# Wilssen_core_v0_202a.net
KiCad netlist of a schematic drawn in EAGLE
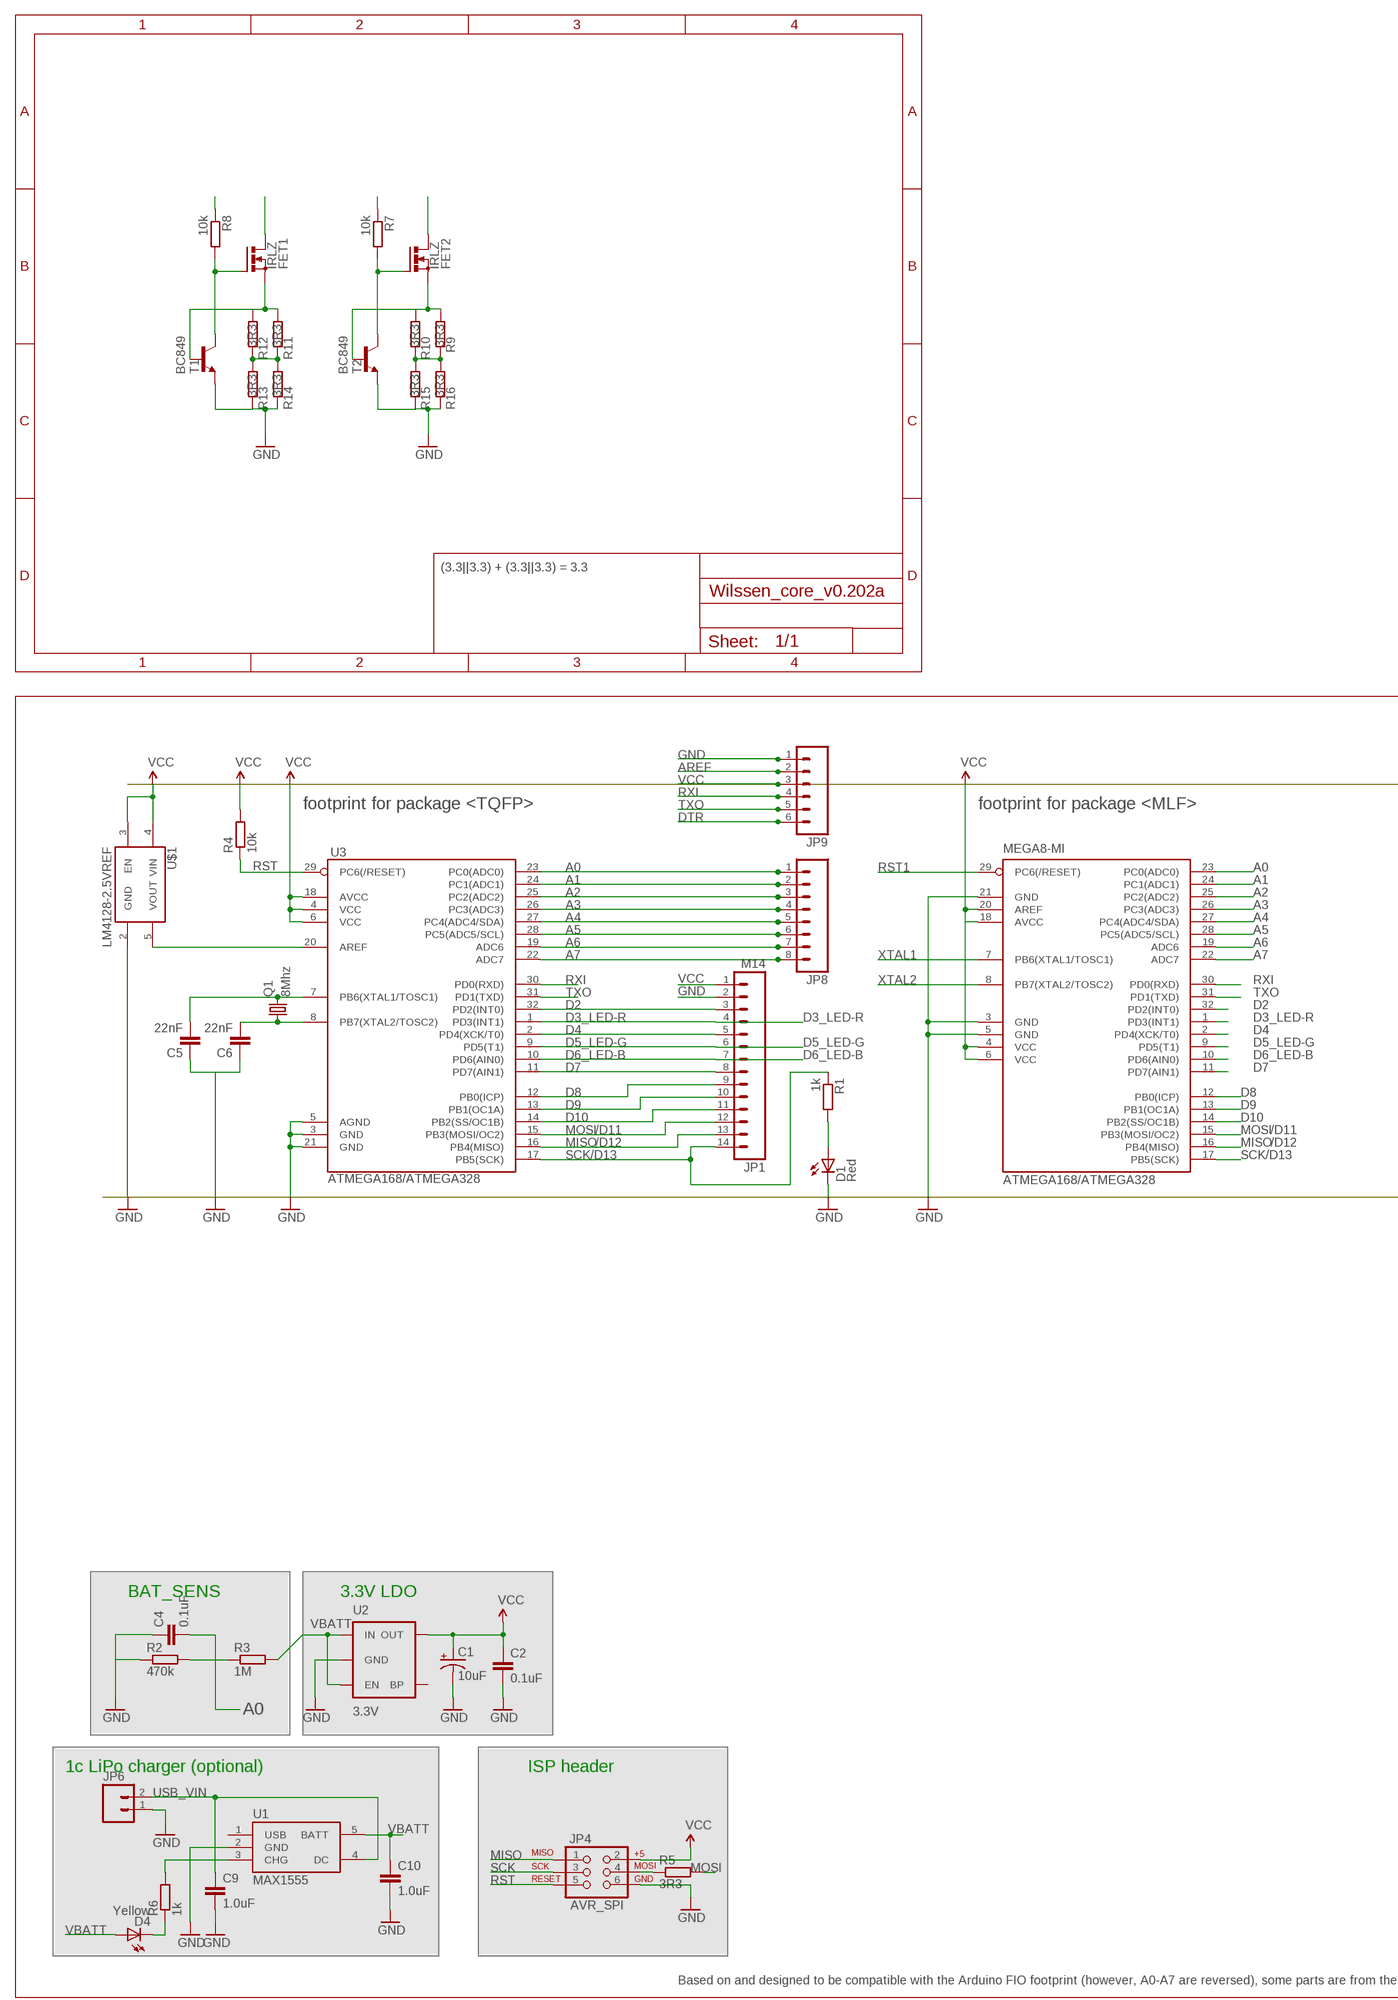
[diagram p0: schematic, sheet 1, part 1 of 2]
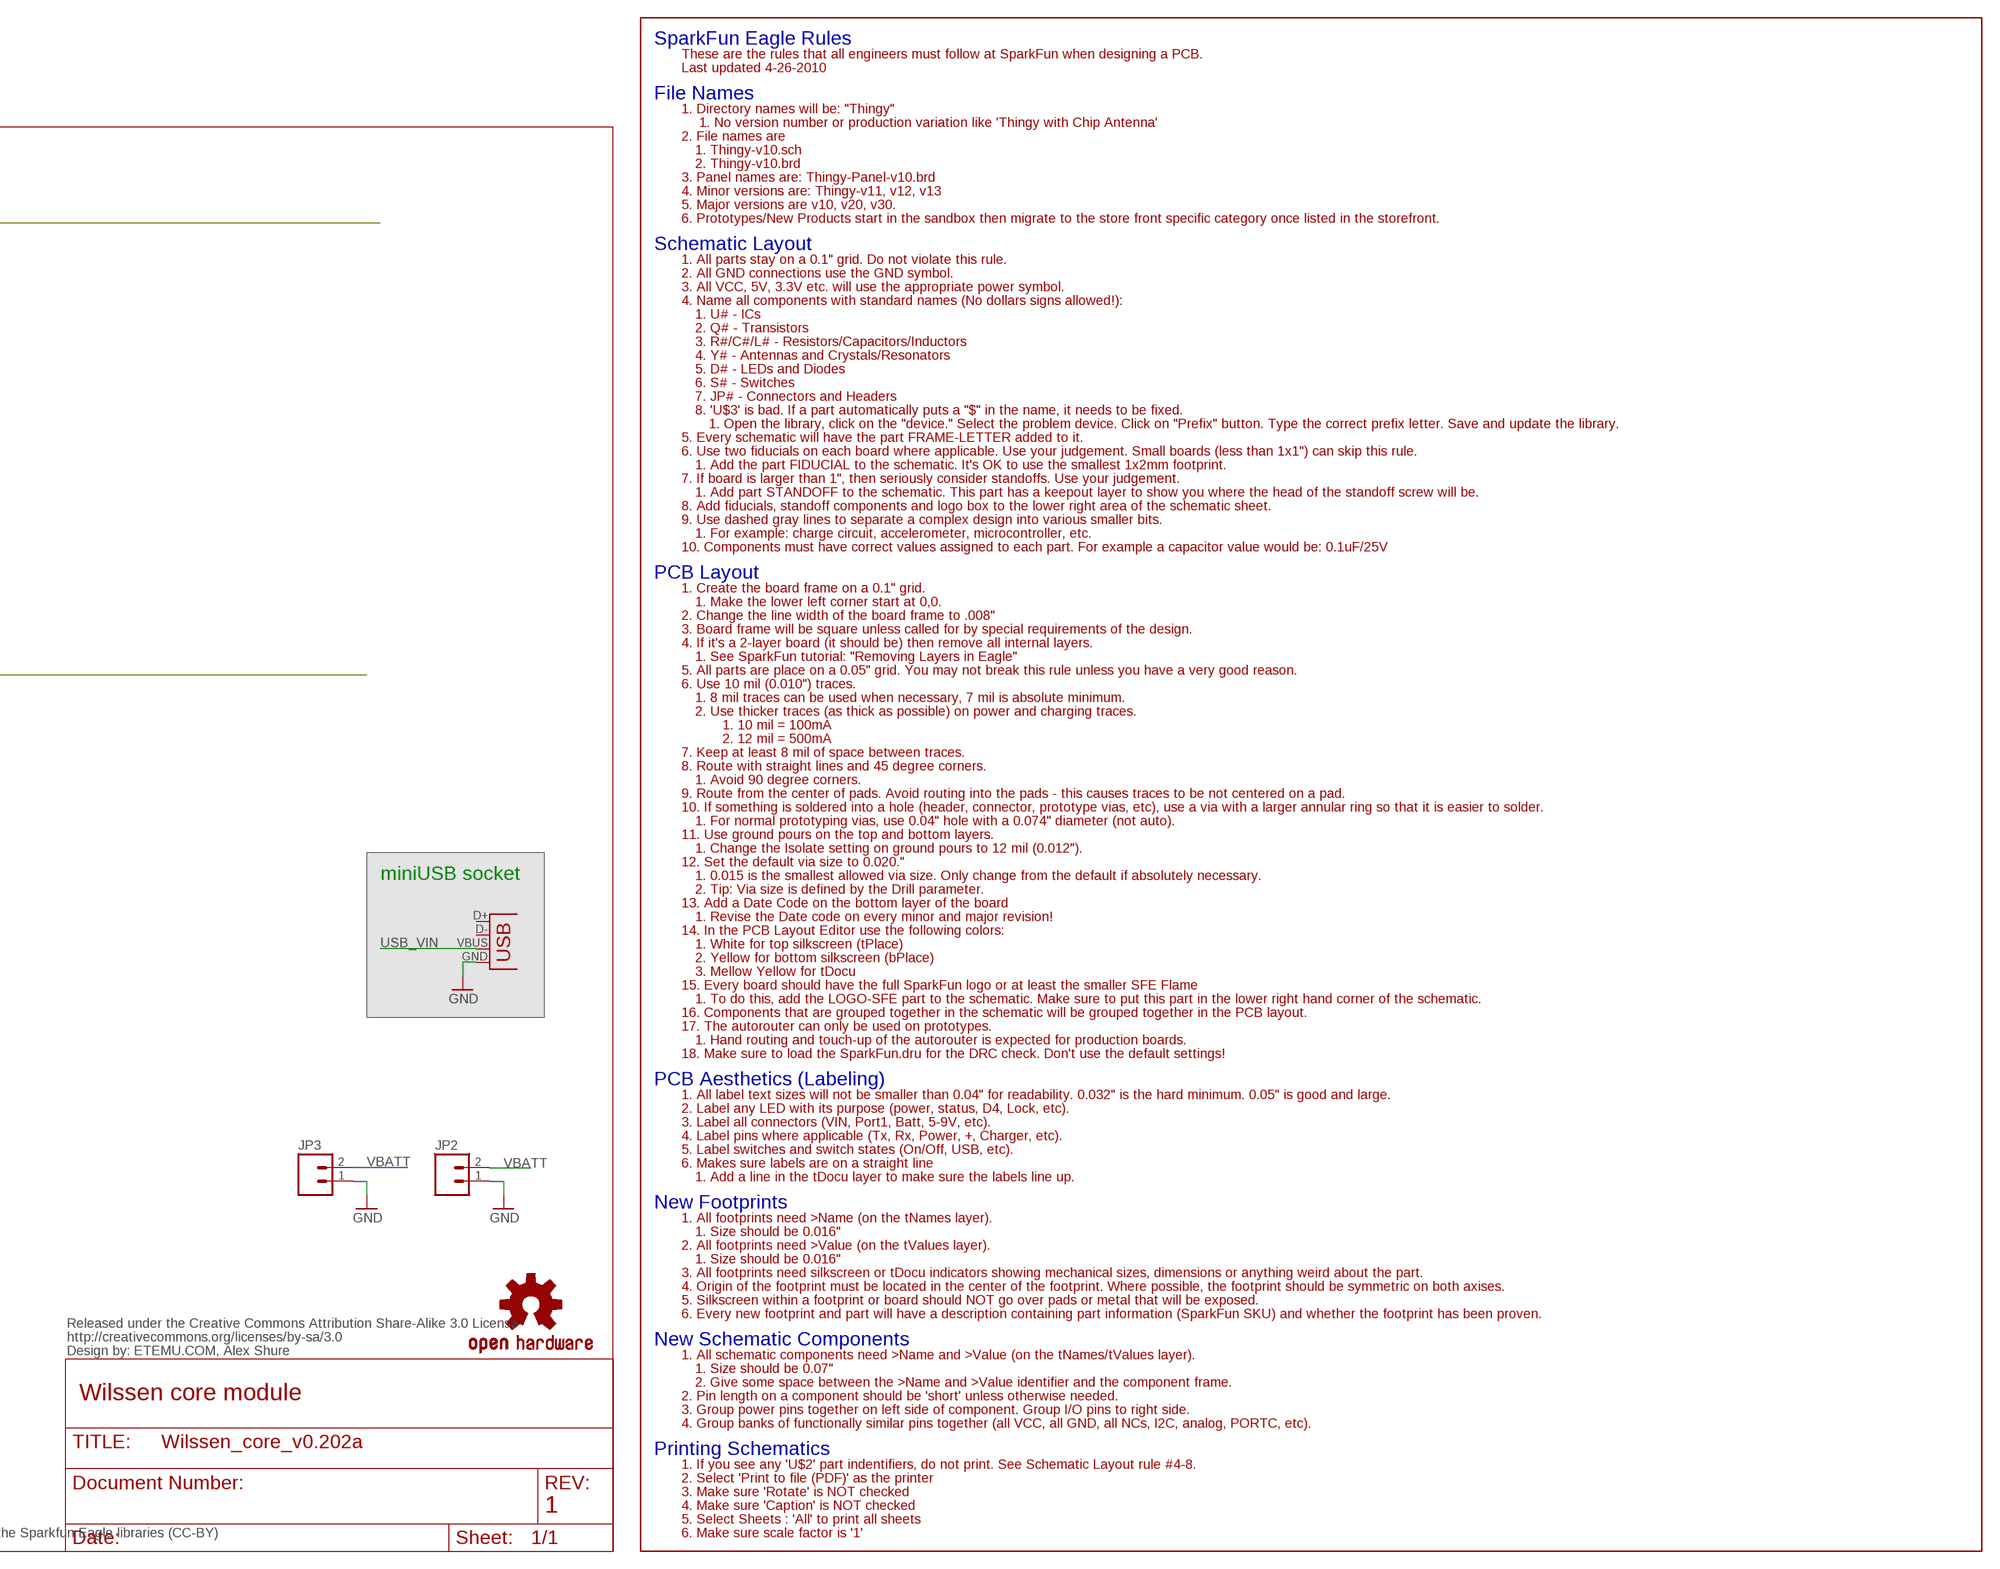
[diagram p1: schematic, sheet 1, part 2 of 2]

(export (version "E")
  (design (tool "Eeschema 10.0.6"))
  (components
    (comp (ref "ATMEGA168/ATMEGA328")
      (value "MEGA8-MI")
      (footprint "eagle-import:MLF32")
      (fields (field (name "MPN") "ATMEGA88PA-MU"))
      (libsource (lib "eagle-import") (part "MEGA8-MI"))
    )
    (comp (ref "C1")
      (value "10uF")
      (footprint "eagle-import:EIA3216")
      (libsource (lib "eagle-import") (part "CAP_POL1206"))
    )
    (comp (ref "C2")
      (value "0.1uF")
      (footprint "eagle-import:0805")
      (libsource (lib "eagle-import") (part "CAP0805"))
    )
    (comp (ref "C4")
      (value "0.1uF")
      (footprint "eagle-import:0805")
      (libsource (lib "eagle-import") (part "CAP0805"))
    )
    (comp (ref "C5")
      (value "22nF")
      (footprint "eagle-import:0805")
      (libsource (lib "eagle-import") (part "CAP0805"))
    )
    (comp (ref "C6")
      (value "22nF")
      (footprint "eagle-import:0805")
      (libsource (lib "eagle-import") (part "CAP0805"))
    )
    (comp (ref "C9")
      (value "1.0uF")
      (footprint "eagle-import:0805")
      (libsource (lib "eagle-import") (part "CAP0805"))
    )
    (comp (ref "C10")
      (value "1.0uF")
      (footprint "eagle-import:0805")
      (libsource (lib "eagle-import") (part "CAP0805"))
    )
    (comp (ref "CC_TEXT1")
      (value "CREATIVE_COMMONS")
      (footprint "eagle-import:CREATIVE_COMMONS")
      (libsource (lib "eagle-import") (part "CREATIVE_COMMONS"))
    )
    (comp (ref "D1")
      (value "Red")
      (footprint "eagle-import:LED-0603")
      (libsource (lib "eagle-import") (part "LED0603"))
    )
    (comp (ref "D4")
      (value "Yellow")
      (footprint "eagle-import:LED-0603")
      (libsource (lib "eagle-import") (part "LED0603"))
    )
    (comp (ref "FET1")
      (value "IRLZ")
      (footprint "eagle-import:TO220BV")
      (libsource (lib "eagle-import") (part "PMOSFET_NTO220BV"))
    )
    (comp (ref "FET2")
      (value "IRLZ")
      (footprint "eagle-import:TO220BV")
      (libsource (lib "eagle-import") (part "PMOSFET_NTO220BV"))
    )
    (comp (ref "JP1")
      (value "M14")
      (footprint "eagle-import:1X14")
      (libsource (lib "eagle-import") (part "M14"))
    )
    (comp (ref "JP2")
      (value "M02PTH")
      (footprint "eagle-import:1X02")
      (libsource (lib "eagle-import") (part "M02PTH"))
    )
    (comp (ref "JP3")
      (value "M02-JST-2MM-SMT")
      (footprint "eagle-import:S2B-PH")
      (libsource (lib "eagle-import") (part "M02-JST-2MM-SMT"))
    )
    (comp (ref "JP4")
      (value "AVR_SPI")
      (footprint "eagle-import:2X3")
      (libsource (lib "eagle-import") (part "AVR_SPI_PRG_6PTH"))
    )
    (comp (ref "JP6")
      (value "M02PTH")
      (footprint "eagle-import:1X02")
      (libsource (lib "eagle-import") (part "M02PTH"))
    )
    (comp (ref "JP8")
      (value "M081X08")
      (footprint "eagle-import:1X08")
      (libsource (lib "eagle-import") (part "M081X08"))
    )
    (comp (ref "JP9")
      (value "M06SIP")
      (footprint "eagle-import:1X06")
      (libsource (lib "eagle-import") (part "M06SIP"))
    )
    (comp (ref "LOGO1")
      (value "OSHW-LOGOS")
      (footprint "eagle-import:OSHW-LOGO-S")
      (libsource (lib "eagle-import") (part "OSHW-LOGOS"))
    )
    (comp (ref "Q1")
      (value "8Mhz")
      (footprint "eagle-import:SM49")
      (libsource (lib "eagle-import") (part "CRYSTALSM49"))
    )
    (comp (ref "R1")
      (value "1k")
      (footprint "eagle-import:R0805")
      (libsource (lib "eagle-import") (part "R-EU_R0805"))
    )
    (comp (ref "R2")
      (value "470k")
      (footprint "eagle-import:R0805")
      (libsource (lib "eagle-import") (part "R-EU_R0805"))
    )
    (comp (ref "R3")
      (value "1M")
      (footprint "eagle-import:R0805")
      (libsource (lib "eagle-import") (part "R-EU_R0805"))
    )
    (comp (ref "R4")
      (value "10k")
      (footprint "eagle-import:R0805")
      (libsource (lib "eagle-import") (part "R-EU_R0805"))
    )
    (comp (ref "R5")
      (value "3R3")
      (footprint "eagle-import:R1206")
      (libsource (lib "eagle-import") (part "R-EU_R1206"))
    )
    (comp (ref "R6")
      (value "1k")
      (footprint "eagle-import:R0805")
      (libsource (lib "eagle-import") (part "R-EU_R0805"))
    )
    (comp (ref "R7")
      (value "10k")
      (footprint "eagle-import:R0805")
      (libsource (lib "eagle-import") (part "resistor_R-EU_R0805"))
    )
    (comp (ref "R8")
      (value "10k")
      (footprint "eagle-import:R0805")
      (libsource (lib "eagle-import") (part "resistor_R-EU_R0805"))
    )
    (comp (ref "R9")
      (value "3R3")
      (footprint "eagle-import:R1206")
      (libsource (lib "eagle-import") (part "resistor_R-EU_R1206"))
    )
    (comp (ref "R10")
      (value "3R3")
      (footprint "eagle-import:R1206")
      (libsource (lib "eagle-import") (part "resistor_R-EU_R1206"))
    )
    (comp (ref "R11")
      (value "3R3")
      (footprint "eagle-import:R1206")
      (libsource (lib "eagle-import") (part "resistor_R-EU_R1206"))
    )
    (comp (ref "R12")
      (value "3R3")
      (footprint "eagle-import:R1206")
      (libsource (lib "eagle-import") (part "resistor_R-EU_R1206"))
    )
    (comp (ref "R13")
      (value "3R3")
      (footprint "eagle-import:R1206")
      (libsource (lib "eagle-import") (part "resistor_R-EU_R1206"))
    )
    (comp (ref "R14")
      (value "3R3")
      (footprint "eagle-import:R1206")
      (libsource (lib "eagle-import") (part "resistor_R-EU_R1206"))
    )
    (comp (ref "R15")
      (value "3R3")
      (footprint "eagle-import:R1206")
      (libsource (lib "eagle-import") (part "resistor_R-EU_R1206"))
    )
    (comp (ref "R16")
      (value "3R3")
      (footprint "eagle-import:R1206")
      (libsource (lib "eagle-import") (part "resistor_R-EU_R1206"))
    )
    (comp (ref "T1")
      (value "BC849")
      (footprint "eagle-import:SOT23")
      (libsource (lib "eagle-import") (part "BC849"))
    )
    (comp (ref "T2")
      (value "BC849")
      (footprint "eagle-import:SOT23")
      (libsource (lib "eagle-import") (part "BC849"))
    )
    (comp (ref "U$1")
      (value "LM4128-2.5VREF")
      (footprint "eagle-import:SOT23-5")
      (libsource (lib "eagle-import") (part "LM4128-2.5VREF"))
    )
    (comp (ref "U1")
      (value "MAX1555")
      (footprint "eagle-import:SOT23-5")
      (libsource (lib "eagle-import") (part "MAX1555"))
    )
    (comp (ref "U2")
      (value "3.3V")
      (footprint "eagle-import:SOT23-5")
      (libsource (lib "eagle-import") (part "V_REG_LDOSMD"))
    )
    (comp (ref "U3")
      (value "ATMEGA168/ATMEGA328")
      (footprint "eagle-import:TQFP32-08")
      (libsource (lib "eagle-import") (part "ATMEGA168"))
    )
    (comp (ref "X1")
      (value "USBSMD")
      (footprint "eagle-import:USB-MINIB")
      (libsource (lib "eagle-import") (part "USBSMD"))
    )
  )
  (nets
    (net (code "1") (name "/A0") (class "Default")
      (node (ref "ATMEGA168/ATMEGA328") (pin "23") (pinfunction "PC0(ADC0)_23") (pintype "bidirectional"))
      (node (ref "C4") (pin "2") (pinfunction "2_2") (pintype "passive"))
      (node (ref "JP8") (pin "1") (pinfunction "1_1") (pintype "passive"))
      (node (ref "R2") (pin "2") (pinfunction "2_2") (pintype "passive"))
      (node (ref "R3") (pin "1") (pinfunction "1_1") (pintype "passive"))
      (node (ref "U3") (pin "23") (pinfunction "PC0(ADC0)_23") (pintype "bidirectional"))
    )
    (net (code "2") (name "/A1") (class "Default")
      (node (ref "ATMEGA168/ATMEGA328") (pin "24") (pinfunction "PC1(ADC1)_24") (pintype "bidirectional"))
      (node (ref "JP8") (pin "2") (pinfunction "2_2") (pintype "passive"))
      (node (ref "U3") (pin "24") (pinfunction "PC1(ADC1)_24") (pintype "bidirectional"))
    )
    (net (code "3") (name "/A2") (class "Default")
      (node (ref "ATMEGA168/ATMEGA328") (pin "25") (pinfunction "PC2(ADC2)_25") (pintype "bidirectional"))
      (node (ref "JP8") (pin "3") (pinfunction "3_3") (pintype "passive"))
      (node (ref "U3") (pin "25") (pinfunction "PC2(ADC2)_25") (pintype "bidirectional"))
    )
    (net (code "4") (name "/A3") (class "Default")
      (node (ref "ATMEGA168/ATMEGA328") (pin "26") (pinfunction "PC3(ADC3)_26") (pintype "bidirectional"))
      (node (ref "JP8") (pin "4") (pinfunction "4_4") (pintype "passive"))
      (node (ref "U3") (pin "26") (pinfunction "PC3(ADC3)_26") (pintype "bidirectional"))
    )
    (net (code "5") (name "/A4") (class "Default")
      (node (ref "ATMEGA168/ATMEGA328") (pin "27") (pinfunction "PC4(ADC4/SDA)_27") (pintype "bidirectional"))
      (node (ref "JP8") (pin "5") (pinfunction "5_5") (pintype "passive"))
      (node (ref "U3") (pin "27") (pinfunction "PC4(ADC4/SDA)_27") (pintype "bidirectional"))
    )
    (net (code "6") (name "/A5") (class "Default")
      (node (ref "ATMEGA168/ATMEGA328") (pin "28") (pinfunction "PC5(ADC5/SCL)_28") (pintype "bidirectional"))
      (node (ref "JP8") (pin "6") (pinfunction "6_6") (pintype "passive"))
      (node (ref "U3") (pin "28") (pinfunction "PC5(ADC5/SCL)_28") (pintype "bidirectional"))
    )
    (net (code "7") (name "/A6") (class "Default")
      (node (ref "ATMEGA168/ATMEGA328") (pin "19") (pinfunction "ADC6_19") (pintype "bidirectional"))
      (node (ref "JP8") (pin "7") (pinfunction "7_7") (pintype "passive"))
      (node (ref "U3") (pin "19") (pinfunction "ADC6_19") (pintype "bidirectional"))
    )
    (net (code "8") (name "/A7") (class "Default")
      (node (ref "ATMEGA168/ATMEGA328") (pin "22") (pinfunction "ADC7_22") (pintype "bidirectional"))
      (node (ref "JP8") (pin "8") (pinfunction "8_8") (pintype "passive"))
      (node (ref "U3") (pin "22") (pinfunction "ADC7_22") (pintype "bidirectional"))
    )
    (net (code "9") (name "/AREF") (class "Default")
      (node (ref "JP9") (pin "2") (pinfunction "2_2") (pintype "passive"))
    )
    (net (code "10") (name "/D2") (class "Default")
      (node (ref "ATMEGA168/ATMEGA328") (pin "32") (pinfunction "PD2(INT0)_32") (pintype "bidirectional"))
      (node (ref "JP1") (pin "3") (pinfunction "3_3") (pintype "passive"))
      (node (ref "U3") (pin "32") (pinfunction "PD2(INT0)_32") (pintype "bidirectional"))
    )
    (net (code "11") (name "/D3_LED-R") (class "Default")
      (node (ref "ATMEGA168/ATMEGA328") (pin "1") (pinfunction "PD3(INT1)_1") (pintype "bidirectional"))
      (node (ref "JP1") (pin "4") (pinfunction "4_4") (pintype "passive"))
      (node (ref "R8") (pin "1") (pinfunction "1_1") (pintype "passive"))
      (node (ref "U3") (pin "1") (pinfunction "PD3(INT1)_1") (pintype "bidirectional"))
    )
    (net (code "12") (name "/D4") (class "Default")
      (node (ref "ATMEGA168/ATMEGA328") (pin "2") (pinfunction "PD4(XCK/T0)_2") (pintype "bidirectional"))
      (node (ref "JP1") (pin "5") (pinfunction "5_5") (pintype "passive"))
      (node (ref "U3") (pin "2") (pinfunction "PD4(XCK/T0)_2") (pintype "bidirectional"))
    )
    (net (code "13") (name "/D5_LED-G") (class "Default")
      (node (ref "ATMEGA168/ATMEGA328") (pin "9") (pinfunction "PD5(T1)_9") (pintype "bidirectional"))
      (node (ref "JP1") (pin "6") (pinfunction "6_6") (pintype "passive"))
      (node (ref "R7") (pin "1") (pinfunction "1_1") (pintype "passive"))
      (node (ref "U3") (pin "9") (pinfunction "PD5(T1)_9") (pintype "bidirectional"))
    )
    (net (code "14") (name "/D6_LED-B") (class "Default")
      (node (ref "ATMEGA168/ATMEGA328") (pin "10") (pinfunction "PD6(AIN0)_10") (pintype "bidirectional"))
      (node (ref "JP1") (pin "7") (pinfunction "7_7") (pintype "passive"))
      (node (ref "U3") (pin "10") (pinfunction "PD6(AIN0)_10") (pintype "bidirectional"))
    )
    (net (code "15") (name "/D7") (class "Default")
      (node (ref "ATMEGA168/ATMEGA328") (pin "11") (pinfunction "PD7(AIN1)_11") (pintype "bidirectional"))
      (node (ref "JP1") (pin "8") (pinfunction "8_8") (pintype "passive"))
      (node (ref "U3") (pin "11") (pinfunction "PD7(AIN1)_11") (pintype "bidirectional"))
    )
    (net (code "16") (name "/D8") (class "Default")
      (node (ref "ATMEGA168/ATMEGA328") (pin "12") (pinfunction "PB0(ICP)_12") (pintype "bidirectional"))
      (node (ref "JP1") (pin "9") (pinfunction "9_9") (pintype "passive"))
      (node (ref "U3") (pin "12") (pinfunction "PB0(ICP)_12") (pintype "bidirectional"))
    )
    (net (code "17") (name "/D9") (class "Default")
      (node (ref "ATMEGA168/ATMEGA328") (pin "13") (pinfunction "PB1(OC1A)_13") (pintype "bidirectional"))
      (node (ref "JP1") (pin "10") (pinfunction "10_10") (pintype "passive"))
      (node (ref "U3") (pin "13") (pinfunction "PB1(OC1A)_13") (pintype "bidirectional"))
    )
    (net (code "18") (name "/D10") (class "Default")
      (node (ref "ATMEGA168/ATMEGA328") (pin "14") (pinfunction "PB2(SS/OC1B)_14") (pintype "bidirectional"))
      (node (ref "JP1") (pin "11") (pinfunction "11_11") (pintype "passive"))
      (node (ref "U3") (pin "14") (pinfunction "PB2(SS/OC1B)_14") (pintype "bidirectional"))
    )
    (net (code "19") (name "/DTR") (class "Default")
      (node (ref "JP9") (pin "6") (pinfunction "6_6") (pintype "passive"))
    )
    (net (code "20") (name "/MISO") (class "Default")
      (node (ref "ATMEGA168/ATMEGA328") (pin "16") (pinfunction "PB4(MISO)_16") (pintype "bidirectional"))
      (node (ref "JP1") (pin "13") (pinfunction "13_13") (pintype "passive"))
      (node (ref "JP4") (pin "1") (pinfunction "1_1") (pintype "passive"))
      (node (ref "U3") (pin "16") (pinfunction "PB4(MISO)_16") (pintype "bidirectional"))
    )
    (net (code "21") (name "/MOSI") (class "Default")
      (node (ref "ATMEGA168/ATMEGA328") (pin "15") (pinfunction "PB3(MOSI/OC2)_15") (pintype "bidirectional"))
      (node (ref "JP1") (pin "12") (pinfunction "12_12") (pintype "passive"))
      (node (ref "R5") (pin "2") (pinfunction "2_2") (pintype "passive"))
      (node (ref "U3") (pin "15") (pinfunction "PB3(MOSI/OC2)_15") (pintype "bidirectional"))
    )
    (net (code "22") (name "/RST") (class "Default")
      (node (ref "JP4") (pin "5") (pinfunction "5_5") (pintype "passive"))
      (node (ref "R4") (pin "1") (pinfunction "1_1") (pintype "passive"))
      (node (ref "U3") (pin "29") (pinfunction "PC6(/RESET)_29") (pintype "bidirectional"))
    )
    (net (code "23") (name "/RST1") (class "Default")
      (node (ref "ATMEGA168/ATMEGA328") (pin "29") (pinfunction "PC6(/RESET)_29") (pintype "bidirectional"))
    )
    (net (code "24") (name "/RXI") (class "Default")
      (node (ref "ATMEGA168/ATMEGA328") (pin "30") (pinfunction "PD0(RXD)_30") (pintype "bidirectional"))
      (node (ref "JP9") (pin "4") (pinfunction "4_4") (pintype "passive"))
      (node (ref "U3") (pin "30") (pinfunction "PD0(RXD)_30") (pintype "bidirectional"))
    )
    (net (code "25") (name "/SCK") (class "Default")
      (node (ref "ATMEGA168/ATMEGA328") (pin "17") (pinfunction "PB5(SCK)_17") (pintype "bidirectional"))
      (node (ref "JP1") (pin "14") (pinfunction "14_14") (pintype "passive"))
      (node (ref "JP4") (pin "3") (pinfunction "3_3") (pintype "passive"))
      (node (ref "R1") (pin "1") (pinfunction "1_1") (pintype "passive"))
      (node (ref "U3") (pin "17") (pinfunction "PB5(SCK)_17") (pintype "bidirectional"))
    )
    (net (code "26") (name "/TXO") (class "Default")
      (node (ref "ATMEGA168/ATMEGA328") (pin "31") (pinfunction "PD1(TXD)_31") (pintype "bidirectional"))
      (node (ref "JP9") (pin "5") (pinfunction "5_5") (pintype "passive"))
      (node (ref "U3") (pin "31") (pinfunction "PD1(TXD)_31") (pintype "bidirectional"))
    )
    (net (code "27") (name "/USB_VIN") (class "Default")
      (node (ref "C9") (pin "1") (pinfunction "1_1") (pintype "passive"))
      (node (ref "JP6") (pin "2") (pinfunction "2_2") (pintype "passive"))
      (node (ref "U1") (pin "4") (pinfunction "DC_4") (pintype "bidirectional"))
      (node (ref "X1") (pin "VBUS") (pinfunction "VBUS_VBUS") (pintype "bidirectional"))
    )
    (net (code "28") (name "/VBATT") (class "Default")
      (node (ref "C10") (pin "1") (pinfunction "1_1") (pintype "passive"))
      (node (ref "D4") (pin "A") (pinfunction "A_A") (pintype "passive"))
      (node (ref "JP2") (pin "2") (pinfunction "2_2") (pintype "passive"))
      (node (ref "JP3") (pin "2") (pinfunction "2_2") (pintype "passive"))
      (node (ref "R3") (pin "2") (pinfunction "2_2") (pintype "passive"))
      (node (ref "U1") (pin "5") (pinfunction "BATT_5") (pintype "bidirectional"))
      (node (ref "U2") (pin "1") (pinfunction "IN_1") (pintype "input"))
      (node (ref "U2") (pin "3") (pinfunction "EN_3") (pintype "input"))
    )
    (net (code "29") (name "/XTAL1") (class "Default")
      (node (ref "ATMEGA168/ATMEGA328") (pin "7") (pinfunction "PB6(XTAL1/TOSC1)_7") (pintype "bidirectional"))
      (node (ref "C5") (pin "2") (pinfunction "2_2") (pintype "passive"))
      (node (ref "Q1") (pin "2") (pinfunction "2_2") (pintype "passive"))
      (node (ref "U3") (pin "7") (pinfunction "PB6(XTAL1/TOSC1)_7") (pintype "bidirectional"))
    )
    (net (code "30") (name "/XTAL2") (class "Default")
      (node (ref "ATMEGA168/ATMEGA328") (pin "8") (pinfunction "PB7(XTAL2/TOSC2)_8") (pintype "bidirectional"))
      (node (ref "C6") (pin "2") (pinfunction "2_2") (pintype "passive"))
      (node (ref "Q1") (pin "1") (pinfunction "1_1") (pintype "passive"))
      (node (ref "U3") (pin "8") (pinfunction "PB7(XTAL2/TOSC2)_8") (pintype "bidirectional"))
    )
    (net (code "31") (name "GND") (class "Default")
      (node (ref "ATMEGA168/ATMEGA328") (pin "21") (pinfunction "GND_21") (pintype "power_in"))
      (node (ref "ATMEGA168/ATMEGA328") (pin "3") (pinfunction "GND_3") (pintype "power_in"))
      (node (ref "ATMEGA168/ATMEGA328") (pin "5") (pinfunction "GND_5") (pintype "power_in"))
      (node (ref "C1") (pin "C") (pinfunction "-_C") (pintype "passive"))
      (node (ref "C10") (pin "2") (pinfunction "2_2") (pintype "passive"))
      (node (ref "C2") (pin "2") (pinfunction "2_2") (pintype "passive"))
      (node (ref "C4") (pin "1") (pinfunction "1_1") (pintype "passive"))
      (node (ref "C5") (pin "1") (pinfunction "1_1") (pintype "passive"))
      (node (ref "C6") (pin "1") (pinfunction "1_1") (pintype "passive"))
      (node (ref "C9") (pin "2") (pinfunction "2_2") (pintype "passive"))
      (node (ref "D1") (pin "C") (pinfunction "C_C") (pintype "passive"))
      (node (ref "JP1") (pin "2") (pinfunction "2_2") (pintype "passive"))
      (node (ref "JP2") (pin "1") (pinfunction "1_1") (pintype "passive"))
      (node (ref "JP3") (pin "1") (pinfunction "1_1") (pintype "passive"))
      (node (ref "JP4") (pin "6") (pinfunction "6_6") (pintype "passive"))
      (node (ref "JP6") (pin "1") (pinfunction "1_1") (pintype "passive"))
      (node (ref "JP9") (pin "1") (pinfunction "1_1") (pintype "passive"))
      (node (ref "R13") (pin "2") (pinfunction "2_2") (pintype "passive"))
      (node (ref "R14") (pin "2") (pinfunction "2_2") (pintype "passive"))
      (node (ref "R15") (pin "2") (pinfunction "2_2") (pintype "passive"))
      (node (ref "R16") (pin "2") (pinfunction "2_2") (pintype "passive"))
      (node (ref "R2") (pin "1") (pinfunction "1_1") (pintype "passive"))
      (node (ref "T1") (pin "2") (pinfunction "E_2") (pintype "passive"))
      (node (ref "T2") (pin "2") (pinfunction "E_2") (pintype "passive"))
      (node (ref "U$1") (pin "2") (pinfunction "GND_2") (pintype "bidirectional"))
      (node (ref "U1") (pin "2") (pinfunction "GND_2") (pintype "bidirectional"))
      (node (ref "U2") (pin "2") (pinfunction "GND_2") (pintype "input"))
      (node (ref "U3") (pin "21") (pinfunction "GND_21") (pintype "bidirectional"))
      (node (ref "U3") (pin "3") (pinfunction "GND_3") (pintype "bidirectional"))
      (node (ref "U3") (pin "5") (pinfunction "AGND_5") (pintype "bidirectional"))
      (node (ref "X1") (pin "GND") (pinfunction "GND_GND") (pintype "bidirectional"))
    )
    (net (code "32") (name "Net-(D1-PadA)") (class "Default")
      (node (ref "D1") (pin "A") (pinfunction "A_A") (pintype "passive"))
      (node (ref "R1") (pin "2") (pinfunction "2_2") (pintype "passive"))
    )
    (net (code "33") (name "Net-(D4-PadC)") (class "Default")
      (node (ref "D4") (pin "C") (pinfunction "C_C") (pintype "passive"))
      (node (ref "R6") (pin "1") (pinfunction "1_1") (pintype "passive"))
    )
    (net (code "34") (name "Net-(JP4-Pad4)") (class "Default")
      (node (ref "JP4") (pin "4") (pinfunction "4_4") (pintype "passive"))
      (node (ref "R5") (pin "1") (pinfunction "1_1") (pintype "passive"))
    )
    (net (code "35") (name "Net-(R10-Pad2)") (class "Default")
      (node (ref "R10") (pin "2") (pinfunction "2_2") (pintype "passive"))
      (node (ref "R15") (pin "1") (pinfunction "1_1") (pintype "passive"))
      (node (ref "R16") (pin "1") (pinfunction "1_1") (pintype "passive"))
      (node (ref "R9") (pin "2") (pinfunction "2_2") (pintype "passive"))
    )
    (net (code "36") (name "Net-(R11-Pad2)") (class "Default")
      (node (ref "R11") (pin "2") (pinfunction "2_2") (pintype "passive"))
      (node (ref "R12") (pin "2") (pinfunction "2_2") (pintype "passive"))
      (node (ref "R13") (pin "1") (pinfunction "1_1") (pintype "passive"))
      (node (ref "R14") (pin "1") (pinfunction "1_1") (pintype "passive"))
    )
    (net (code "37") (name "Net-(T1-B)") (class "Default")
      (node (ref "FET1") (pin "S") (pinfunction "S_S") (pintype "passive"))
      (node (ref "R11") (pin "1") (pinfunction "1_1") (pintype "passive"))
      (node (ref "R12") (pin "1") (pinfunction "1_1") (pintype "passive"))
      (node (ref "T1") (pin "1") (pinfunction "B_1") (pintype "passive"))
    )
    (net (code "38") (name "Net-(T1-C)") (class "Default")
      (node (ref "FET1") (pin "G") (pinfunction "G_G") (pintype "passive"))
      (node (ref "R8") (pin "2") (pinfunction "2_2") (pintype "passive"))
      (node (ref "T1") (pin "3") (pinfunction "C_3") (pintype "passive"))
    )
    (net (code "39") (name "Net-(T2-B)") (class "Default")
      (node (ref "FET2") (pin "S") (pinfunction "S_S") (pintype "passive"))
      (node (ref "R10") (pin "1") (pinfunction "1_1") (pintype "passive"))
      (node (ref "R9") (pin "1") (pinfunction "1_1") (pintype "passive"))
      (node (ref "T2") (pin "1") (pinfunction "B_1") (pintype "passive"))
    )
    (net (code "40") (name "Net-(T2-C)") (class "Default")
      (node (ref "FET2") (pin "G") (pinfunction "G_G") (pintype "passive"))
      (node (ref "R7") (pin "2") (pinfunction "2_2") (pintype "passive"))
      (node (ref "T2") (pin "3") (pinfunction "C_3") (pintype "passive"))
    )
    (net (code "41") (name "Net-(U$1-VOUT)") (class "Default")
      (node (ref "U$1") (pin "5") (pinfunction "VOUT_5") (pintype "bidirectional"))
      (node (ref "U3") (pin "20") (pinfunction "AREF_20") (pintype "bidirectional"))
    )
    (net (code "42") (name "Net-(U1-CHG)") (class "Default")
      (node (ref "R6") (pin "2") (pinfunction "2_2") (pintype "passive"))
      (node (ref "U1") (pin "3") (pinfunction "CHG_3") (pintype "bidirectional"))
    )
    (net (code "43") (name "VCC") (class "Default")
      (node (ref "ATMEGA168/ATMEGA328") (pin "18") (pinfunction "AVCC_18") (pintype "power_in"))
      (node (ref "ATMEGA168/ATMEGA328") (pin "20") (pinfunction "AREF_20") (pintype "passive"))
      (node (ref "ATMEGA168/ATMEGA328") (pin "4") (pinfunction "VCC_4") (pintype "power_in"))
      (node (ref "ATMEGA168/ATMEGA328") (pin "6") (pinfunction "VCC_6") (pintype "power_in"))
      (node (ref "C1") (pin "A") (pinfunction "+_A") (pintype "passive"))
      (node (ref "C2") (pin "1") (pinfunction "1_1") (pintype "passive"))
      (node (ref "JP1") (pin "1") (pinfunction "1_1") (pintype "passive"))
      (node (ref "JP4") (pin "2") (pinfunction "2_2") (pintype "passive"))
      (node (ref "JP9") (pin "3") (pinfunction "3_3") (pintype "passive"))
      (node (ref "R4") (pin "2") (pinfunction "2_2") (pintype "passive"))
      (node (ref "U$1") (pin "3") (pinfunction "EN_3") (pintype "bidirectional"))
      (node (ref "U$1") (pin "4") (pinfunction "VIN_4") (pintype "bidirectional"))
      (node (ref "U2") (pin "5") (pinfunction "OUT_5") (pintype "passive"))
      (node (ref "U3") (pin "18") (pinfunction "AVCC_18") (pintype "bidirectional"))
      (node (ref "U3") (pin "4") (pinfunction "VCC_4") (pintype "bidirectional"))
      (node (ref "U3") (pin "6") (pinfunction "VCC_6") (pintype "bidirectional"))
    )
    (net (code "44") (name "unconnected-(FET1-PadD)") (class "Default")
      (node (ref "FET1") (pin "D") (pinfunction "D_D") (pintype "passive"))
    )
    (net (code "45") (name "unconnected-(FET2-PadD)") (class "Default")
      (node (ref "FET2") (pin "D") (pinfunction "D_D") (pintype "passive"))
    )
    (net (code "46") (name "unconnected-(U1-USB-Pad1)") (class "Default")
      (node (ref "U1") (pin "1") (pinfunction "USB_1") (pintype "bidirectional"))
    )
    (net (code "47") (name "unconnected-(U2-BP-Pad4)") (class "Default")
      (node (ref "U2") (pin "4") (pinfunction "BP_4") (pintype "input"))
    )
    (net (code "48") (name "unconnected-(X1-PadD+)") (class "Default")
      (node (ref "X1") (pin "D+") (pinfunction "D+_D+") (pintype "bidirectional"))
    )
    (net (code "49") (name "unconnected-(X1-PadD-)") (class "Default")
      (node (ref "X1") (pin "D-") (pinfunction "D-_D-") (pintype "bidirectional"))
    )
  )
)
